# NAVMAN-GPSBOARD.net
KiCad netlist of a schematic drawn in EAGLE
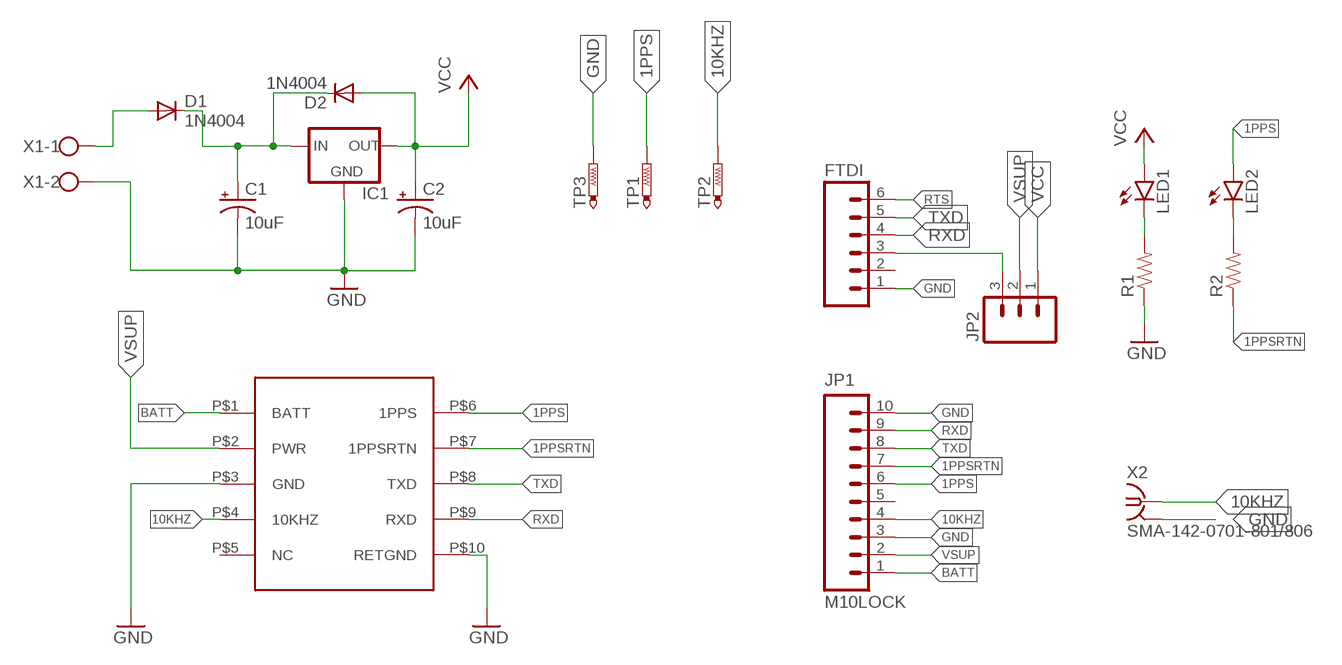
[diagram p0: schematic, sheet 1]

(export (version "E")
  (design (tool "Eeschema 10.0.6"))
  (components
    (comp (ref "C1")
      (value "10uF")
      (footprint "eagle-import:CPOL-RADIAL-10UF-25V")
      (libsource (lib "eagle-import") (part "10UF-25V-20%(PTH)"))
    )
    (comp (ref "C2")
      (value "10uF")
      (footprint "eagle-import:CPOL-RADIAL-10UF-25V")
      (libsource (lib "eagle-import") (part "10UF-25V-20%(PTH)"))
    )
    (comp (ref "D1")
      (value "1N4004")
      (footprint "eagle-import:DO41-10")
      (libsource (lib "eagle-import") (part "1N4004"))
    )
    (comp (ref "D2")
      (value "1N4004")
      (footprint "eagle-import:DO41-10")
      (libsource (lib "eagle-import") (part "1N4004"))
    )
    (comp (ref "FTDI")
      (value "M06LOCK")
      (footprint "eagle-import:1X06_LOCK")
      (libsource (lib "eagle-import") (part "M06LOCK"))
    )
    (comp (ref "IC1")
      (value "V_REG_78XXSINK")
      (footprint "eagle-import:TO220-IGO")
      (libsource (lib "eagle-import") (part "V_REG_78XXSINK"))
    )
    (comp (ref "JP1")
      (value "M10LOCK")
      (footprint "eagle-import:1X10_LOCK")
      (libsource (lib "eagle-import") (part "M10LOCK"))
    )
    (comp (ref "JP2")
      (value "M03LOCK")
      (footprint "eagle-import:1X03_LOCK")
      (libsource (lib "eagle-import") (part "M03LOCK"))
    )
    (comp (ref "LED1")
      (value "LED5MM")
      (footprint "eagle-import:LED5MM")
      (libsource (lib "eagle-import") (part "LED5MM"))
    )
    (comp (ref "LED2")
      (value "LED5MM")
      (footprint "eagle-import:LED5MM")
      (libsource (lib "eagle-import") (part "LED5MM"))
    )
    (comp (ref "R1")
      (value "RESISTORPTH-1/4W")
      (footprint "eagle-import:AXIAL-0.4")
      (libsource (lib "eagle-import") (part "RESISTORPTH-1/4W"))
    )
    (comp (ref "R2")
      (value "RESISTORPTH-1/4W")
      (footprint "eagle-import:AXIAL-0.4")
      (libsource (lib "eagle-import") (part "RESISTORPTH-1/4W"))
    )
    (comp (ref "TP1")
      (value "PTR1PAD1-20Y")
      (footprint "eagle-import:P1-20Y")
      (libsource (lib "eagle-import") (part "PTR1PAD1-20Y"))
    )
    (comp (ref "TP2")
      (value "PTR1PAD1-20Y")
      (footprint "eagle-import:P1-20Y")
      (libsource (lib "eagle-import") (part "PTR1PAD1-20Y"))
    )
    (comp (ref "TP3")
      (value "PTR1PAD1-20Y")
      (footprint "eagle-import:P1-20Y")
      (libsource (lib "eagle-import") (part "PTR1PAD1-20Y"))
    )
    (comp (ref "TU60-D001")
      (value "NAVMANJUPITERTU60")
      (footprint "eagle-import:TU60-D001")
      (libsource (lib "eagle-import") (part "NAVMANJUPITERTU60"))
    )
    (comp (ref "X1")
      (value "W237-102")
      (footprint "eagle-import:W237-102")
      (fields (field (name "MPN") "237-102"))
      (libsource (lib "eagle-import") (part "W237-102"))
    )
    (comp (ref "X2")
      (value "SMA-142-0701-801/806")
      (footprint "eagle-import:J502-ND-142-0701-801_806")
      (fields (field (name "MF") "JOHNSON COMPONENTS") (field (name "MPN") "142-0701-801"))
      (libsource (lib "eagle-import") (part "SMA-142-0701-801/806"))
    )
  )
  (nets
    (net (code "1") (name "1PPS") (class "Default")
      (node (ref "JP1") (pin "6") (pinfunction "6_6") (pintype "passive"))
      (node (ref "LED2") (pin "A") (pinfunction "A_A") (pintype "passive"))
      (node (ref "TP1") (pin "TP") (pinfunction "TP_TP") (pintype "input"))
      (node (ref "TU60-D001") (pin "P$6") (pinfunction "1PPS_P$6") (pintype "output"))
    )
    (net (code "2") (name "1PPSRTN") (class "Default")
      (node (ref "JP1") (pin "7") (pinfunction "7_7") (pintype "passive"))
      (node (ref "R2") (pin "P$1") (pinfunction "1_P$1") (pintype "passive"))
      (node (ref "TU60-D001") (pin "P$7") (pinfunction "1PPSRTN_P$7") (pintype "input"))
    )
    (net (code "3") (name "10KHZ") (class "Default")
      (node (ref "JP1") (pin "4") (pinfunction "4_4") (pintype "passive"))
      (node (ref "TP2") (pin "TP") (pinfunction "TP_TP") (pintype "input"))
      (node (ref "TU60-D001") (pin "P$4") (pinfunction "10KHZ_P$4") (pintype "output"))
      (node (ref "X2") (pin "1") (pinfunction "1_1") (pintype "passive"))
    )
    (net (code "4") (name "BATT") (class "Default")
      (node (ref "JP1") (pin "1") (pinfunction "1_1") (pintype "passive"))
      (node (ref "TU60-D001") (pin "P$1") (pinfunction "BATT_P$1") (pintype "power_in"))
    )
    (net (code "5") (name "GND") (class "Default")
      (node (ref "C1") (pin "2") (pinfunction "-_2") (pintype "passive"))
      (node (ref "C2") (pin "2") (pinfunction "-_2") (pintype "passive"))
      (node (ref "FTDI") (pin "1") (pinfunction "1_1") (pintype "passive"))
      (node (ref "IC1") (pin "GND") (pinfunction "GND_GND") (pintype "input"))
      (node (ref "JP1") (pin "10") (pinfunction "10_10") (pintype "passive"))
      (node (ref "JP1") (pin "3") (pinfunction "3_3") (pintype "passive"))
      (node (ref "R1") (pin "P$1") (pinfunction "1_P$1") (pintype "passive"))
      (node (ref "TP3") (pin "TP") (pinfunction "TP_TP") (pintype "input"))
      (node (ref "TU60-D001") (pin "P$10") (pinfunction "RETGND_P$10") (pintype "power_in"))
      (node (ref "TU60-D001") (pin "P$3") (pinfunction "GND_P$3") (pintype "power_in"))
      (node (ref "X1") (pin "2") (pinfunction "KL_2") (pintype "passive"))
      (node (ref "X2") (pin "G@1") (pinfunction "2_G@1") (pintype "passive"))
      (node (ref "X2") (pin "G@2") (pinfunction "2_G@2") (pintype "passive"))
      (node (ref "X2") (pin "G@3") (pinfunction "2_G@3") (pintype "passive"))
      (node (ref "X2") (pin "G@4") (pinfunction "2_G@4") (pintype "passive"))
    )
    (net (code "6") (name "Net-(C1-+)") (class "Default")
      (node (ref "C1") (pin "1") (pinfunction "+_1") (pintype "passive"))
      (node (ref "D1") (pin "C") (pinfunction "C_C") (pintype "passive"))
      (node (ref "D2") (pin "C") (pinfunction "C_C") (pintype "passive"))
      (node (ref "IC1") (pin "IN") (pinfunction "IN_IN") (pintype "input"))
    )
    (net (code "7") (name "Net-(FTDI-Pad3)") (class "Default")
      (node (ref "FTDI") (pin "3") (pinfunction "3_3") (pintype "passive"))
      (node (ref "JP2") (pin "3") (pinfunction "3_3") (pintype "passive"))
    )
    (net (code "8") (name "Net-(LED1-C)") (class "Default")
      (node (ref "LED1") (pin "K") (pinfunction "C_K") (pintype "passive"))
      (node (ref "R1") (pin "P$2") (pinfunction "2_P$2") (pintype "passive"))
    )
    (net (code "9") (name "Net-(LED2-C)") (class "Default")
      (node (ref "LED2") (pin "K") (pinfunction "C_K") (pintype "passive"))
      (node (ref "R2") (pin "P$2") (pinfunction "2_P$2") (pintype "passive"))
    )
    (net (code "10") (name "Net-(X1A-KL)") (class "Default")
      (node (ref "D1") (pin "A") (pinfunction "A_A") (pintype "passive"))
      (node (ref "X1") (pin "1") (pinfunction "KL_1") (pintype "passive"))
    )
    (net (code "11") (name "RTS") (class "Default")
      (node (ref "FTDI") (pin "6") (pinfunction "6_6") (pintype "passive"))
    )
    (net (code "12") (name "RXD") (class "Default")
      (node (ref "FTDI") (pin "4") (pinfunction "4_4") (pintype "passive"))
      (node (ref "JP1") (pin "9") (pinfunction "9_9") (pintype "passive"))
      (node (ref "TU60-D001") (pin "P$9") (pinfunction "RXD_P$9") (pintype "input"))
    )
    (net (code "13") (name "TXD") (class "Default")
      (node (ref "FTDI") (pin "5") (pinfunction "5_5") (pintype "passive"))
      (node (ref "JP1") (pin "8") (pinfunction "8_8") (pintype "passive"))
      (node (ref "TU60-D001") (pin "P$8") (pinfunction "TXD_P$8") (pintype "output"))
    )
    (net (code "14") (name "VCC") (class "Default")
      (node (ref "C2") (pin "1") (pinfunction "+_1") (pintype "passive"))
      (node (ref "D2") (pin "A") (pinfunction "A_A") (pintype "passive"))
      (node (ref "IC1") (pin "OUT") (pinfunction "OUT_OUT") (pintype "output"))
      (node (ref "JP2") (pin "1") (pinfunction "1_1") (pintype "passive"))
      (node (ref "LED1") (pin "A") (pinfunction "A_A") (pintype "passive"))
    )
    (net (code "15") (name "VSUP") (class "Default")
      (node (ref "JP1") (pin "2") (pinfunction "2_2") (pintype "passive"))
      (node (ref "JP2") (pin "2") (pinfunction "2_2") (pintype "passive"))
      (node (ref "TU60-D001") (pin "P$2") (pinfunction "PWR_P$2") (pintype "power_in"))
    )
    (net (code "16") (name "unconnected-(FTDI-Pad2)") (class "Default")
      (node (ref "FTDI") (pin "2") (pinfunction "2_2") (pintype "passive"))
    )
    (net (code "17") (name "unconnected-(JP1-Pad5)") (class "Default")
      (node (ref "JP1") (pin "5") (pinfunction "5_5") (pintype "passive"))
    )
    (net (code "18") (name "unconnected-(TU60-D001-NC-PadP$5)") (class "Default")
      (node (ref "TU60-D001") (pin "P$5") (pinfunction "NC_P$5") (pintype "no_connect"))
    )
  )
)
